# 3V3_LDO.net
KiCad netlist of a schematic drawn in Altium Designer
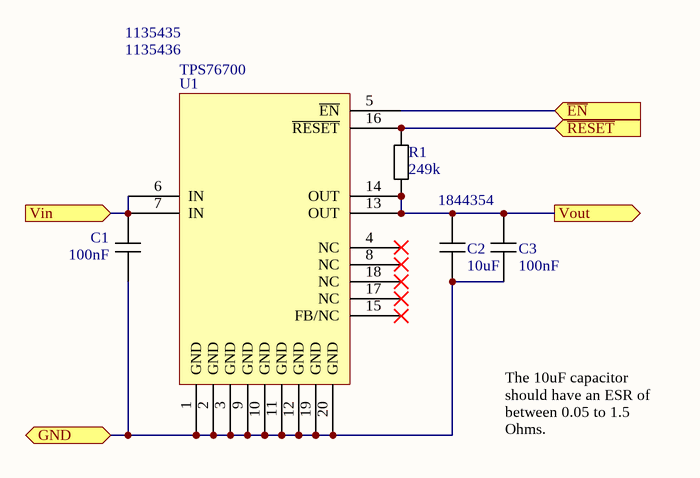
[diagram p0: 3V3_LDO.SchDoc]

(export (version "E")
  (design (tool "Eeschema 10.0.6"))
  (components
    (comp (ref "C1")
      (value "100nF")
      (footprint "0805 Cap")
      (description "0805 MLCC - X7R, 10%")
      (fields (field (name "Comment") "0805 Cap"))
      (libsource (lib "Schlib1") (part "0805 MLCC - X7R, 10%"))
    )
    (comp (ref "C2")
      (value "10uF")
      (footprint "1210 Cap")
      (description "1210 MLCC - X7R, 10%")
      (fields (field (name "SUPPLIER PART NUMBER 1") "1844354") (field (name "Comment") "1210 Cap"))
      (libsource (lib "Schlib1") (part "1210 MLCC - X7R, 10%"))
    )
    (comp (ref "C3")
      (value "100nF")
      (footprint "0805 Cap")
      (description "0805 MLCC - X7R, 10%")
      (fields (field (name "Comment") "0805 Cap"))
      (libsource (lib "Schlib1") (part "0805 MLCC - X7R, 10%"))
    )
    (comp (ref "R1")
      (value "249k")
      (footprint "0805 Resistor")
      (description "0805 Thick Film Resistor 1%")
      (fields (field (name "Comment") "0805 Resistor"))
      (libsource (lib "Schlib1") (part "0805 Thick Film Resistor 1%"))
    )
    (comp (ref "U1")
      (value "TPS76700")
      (footprint "SOP-20 TPS76700")
      (description "LDO Regulator - ER")
      (fields
        (field (name "SUPPLIER PART NUMBER 1") "1135436")
        (field (name "SUPPLIER PART NUMBER 2") "1135435")
      )
      (libsource (lib "Schlib1") (part "TPS76700"))
    )
  )
  (nets
    (net (code "1") (name "/GND") (class "Default")
      (node (ref "C1") (pin "1") (pinfunction "1_1") (pintype "passive"))
      (node (ref "C2") (pin "1") (pinfunction "1_1") (pintype "passive"))
      (node (ref "C3") (pin "1") (pinfunction "1_1") (pintype "passive"))
      (node (ref "U1") (pin "1") (pinfunction "GND_1") (pintype "passive"))
      (node (ref "U1") (pin "10") (pinfunction "GND_10") (pintype "passive"))
      (node (ref "U1") (pin "11") (pinfunction "GND_11") (pintype "passive"))
      (node (ref "U1") (pin "12") (pinfunction "GND_12") (pintype "passive"))
      (node (ref "U1") (pin "19") (pinfunction "GND_19") (pintype "passive"))
      (node (ref "U1") (pin "2") (pinfunction "GND_2") (pintype "passive"))
      (node (ref "U1") (pin "20") (pinfunction "GND_20") (pintype "passive"))
      (node (ref "U1") (pin "3") (pinfunction "GND_3") (pintype "passive"))
      (node (ref "U1") (pin "9") (pinfunction "GND_9") (pintype "passive"))
    )
    (net (code "2") (name "/Vin") (class "Default")
      (node (ref "C1") (pin "2") (pinfunction "2_2") (pintype "passive"))
      (node (ref "U1") (pin "6") (pinfunction "IN_6") (pintype "passive"))
      (node (ref "U1") (pin "7") (pinfunction "IN_7") (pintype "passive"))
    )
    (net (code "3") (name "/Vout") (class "Default")
      (node (ref "C2") (pin "2") (pinfunction "2_2") (pintype "passive"))
      (node (ref "C3") (pin "2") (pinfunction "2_2") (pintype "passive"))
      (node (ref "R1") (pin "1") (pinfunction "1_1") (pintype "passive"))
      (node (ref "U1") (pin "13") (pinfunction "OUT_13") (pintype "passive"))
      (node (ref "U1") (pin "14") (pinfunction "OUT_14") (pintype "passive"))
    )
    (net (code "4") (name "/~{EN}") (class "Default")
      (node (ref "U1") (pin "5") (pinfunction "~{EN}_5") (pintype "passive"))
    )
    (net (code "5") (name "/~{RESET}") (class "Default")
      (node (ref "R1") (pin "2") (pinfunction "2_2") (pintype "passive"))
      (node (ref "U1") (pin "16") (pinfunction "~{RESET}_16") (pintype "passive"))
    )
    (net (code "6") (name "unconnected-(U1-FB{slash}NC-Pad15)") (class "Default")
      (node (ref "U1") (pin "15") (pinfunction "FB/NC_15") (pintype "passive+no_connect"))
    )
    (net (code "7") (name "unconnected-(U1-NC-Pad4)") (class "Default")
      (node (ref "U1") (pin "4") (pinfunction "NC_4") (pintype "passive+no_connect"))
    )
    (net (code "8") (name "unconnected-(U1-NC-Pad8)") (class "Default")
      (node (ref "U1") (pin "8") (pinfunction "NC_8") (pintype "passive+no_connect"))
    )
    (net (code "9") (name "unconnected-(U1-NC-Pad17)") (class "Default")
      (node (ref "U1") (pin "17") (pinfunction "NC_17") (pintype "passive+no_connect"))
    )
    (net (code "10") (name "unconnected-(U1-NC-Pad18)") (class "Default")
      (node (ref "U1") (pin "18") (pinfunction "NC_18") (pintype "passive+no_connect"))
    )
  )
)
